# zxld381-boost-driver-13mm.net
KiCad netlist of a schematic drawn in EAGLE
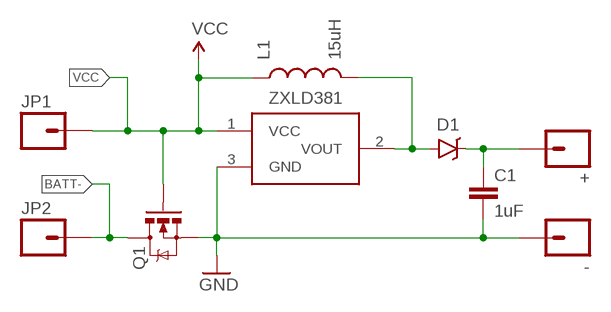
[diagram p0: schematic, sheet 1]

(export (version "E")
  (design (tool "Eeschema 10.0.6"))
  (components
    (comp (ref "+")
      (value "M01PTH-KIT")
      (footprint "eagle-import:1X01-KIT")
      (libsource (lib "eagle-import") (part "M01PTH-KIT"))
    )
    (comp (ref "-")
      (value "M01NOSILK-KIT")
      (footprint "eagle-import:1X01NS-KIT")
      (libsource (lib "eagle-import") (part "M01NOSILK-KIT"))
    )
    (comp (ref "C1")
      (value "1uF")
      (footprint "eagle-import:C0805")
      (libsource (lib "eagle-import") (part "CAPACITOR-CERAMICC0805"))
    )
    (comp (ref "D1")
      (value "PMEG4005EJ")
      (footprint "eagle-import:SOD-323")
      (libsource (lib "eagle-import") (part "DIODE-SCHOTTKY-PMEG4005EJ"))
    )
    (comp (ref "JP1")
      (value "M01NOT-A-VIA-NOPE")
      (footprint "eagle-import:1X01_NOSILK_NOSTOP")
      (libsource (lib "eagle-import") (part "M01NOT-A-VIA-NOPE"))
    )
    (comp (ref "JP2")
      (value "M01NOT-A-VIA-NOPE")
      (footprint "eagle-import:1X01_NOSILK_NOSTOP")
      (libsource (lib "eagle-import") (part "M01NOT-A-VIA-NOPE"))
    )
    (comp (ref "L1")
      (value "15uH")
      (footprint "eagle-import:0805")
      (libsource (lib "eagle-import") (part "INDUCTOR0805"))
    )
    (comp (ref "Q1")
      (value "MOSFET-NCHANNELRYM002N05")
      (footprint "eagle-import:VMT3")
      (libsource (lib "eagle-import") (part "MOSFET-NCHANNELRYM002N05"))
    )
    (comp (ref "ZXLD381")
      (value "ZXLD381")
      (footprint "eagle-import:SOT23-3")
      (libsource (lib "eagle-import") (part "ZXLD381"))
    )
  )
  (nets
    (net (code "1") (name "BATT-") (class "Default")
      (node (ref "JP2") (pin "P$1") (pinfunction "1_P$1") (pintype "passive"))
      (node (ref "Q1") (pin "3") (pinfunction "D_3") (pintype "passive"))
    )
    (net (code "2") (name "GND") (class "Default")
      (node (ref "-") (pin "1") (pinfunction "1_1") (pintype "passive"))
      (node (ref "C1") (pin "2") (pinfunction "2_2") (pintype "passive"))
      (node (ref "Q1") (pin "2") (pinfunction "S_2") (pintype "passive"))
      (node (ref "ZXLD381") (pin "3") (pinfunction "GND_3") (pintype "bidirectional"))
    )
    (net (code "3") (name "Net-(+-Pad1)") (class "Default")
      (node (ref "+") (pin "1") (pinfunction "1_1") (pintype "passive"))
      (node (ref "C1") (pin "1") (pinfunction "1_1") (pintype "passive"))
      (node (ref "D1") (pin "C") (pinfunction "C_C") (pintype "passive"))
    )
    (net (code "4") (name "Net-(ZXLD381-VOUT)") (class "Default")
      (node (ref "D1") (pin "A") (pinfunction "A_A") (pintype "passive"))
      (node (ref "L1") (pin "2") (pinfunction "2_2") (pintype "passive"))
      (node (ref "ZXLD381") (pin "2") (pinfunction "VOUT_2") (pintype "bidirectional"))
    )
    (net (code "5") (name "VCC") (class "Default")
      (node (ref "JP1") (pin "P$1") (pinfunction "1_P$1") (pintype "passive"))
      (node (ref "L1") (pin "1") (pinfunction "1_1") (pintype "passive"))
      (node (ref "Q1") (pin "1") (pinfunction "G_1") (pintype "passive"))
      (node (ref "ZXLD381") (pin "1") (pinfunction "VCC_1") (pintype "bidirectional"))
    )
  )
)
